# CPU.net
KiCad netlist of a schematic drawn in Altium Designer
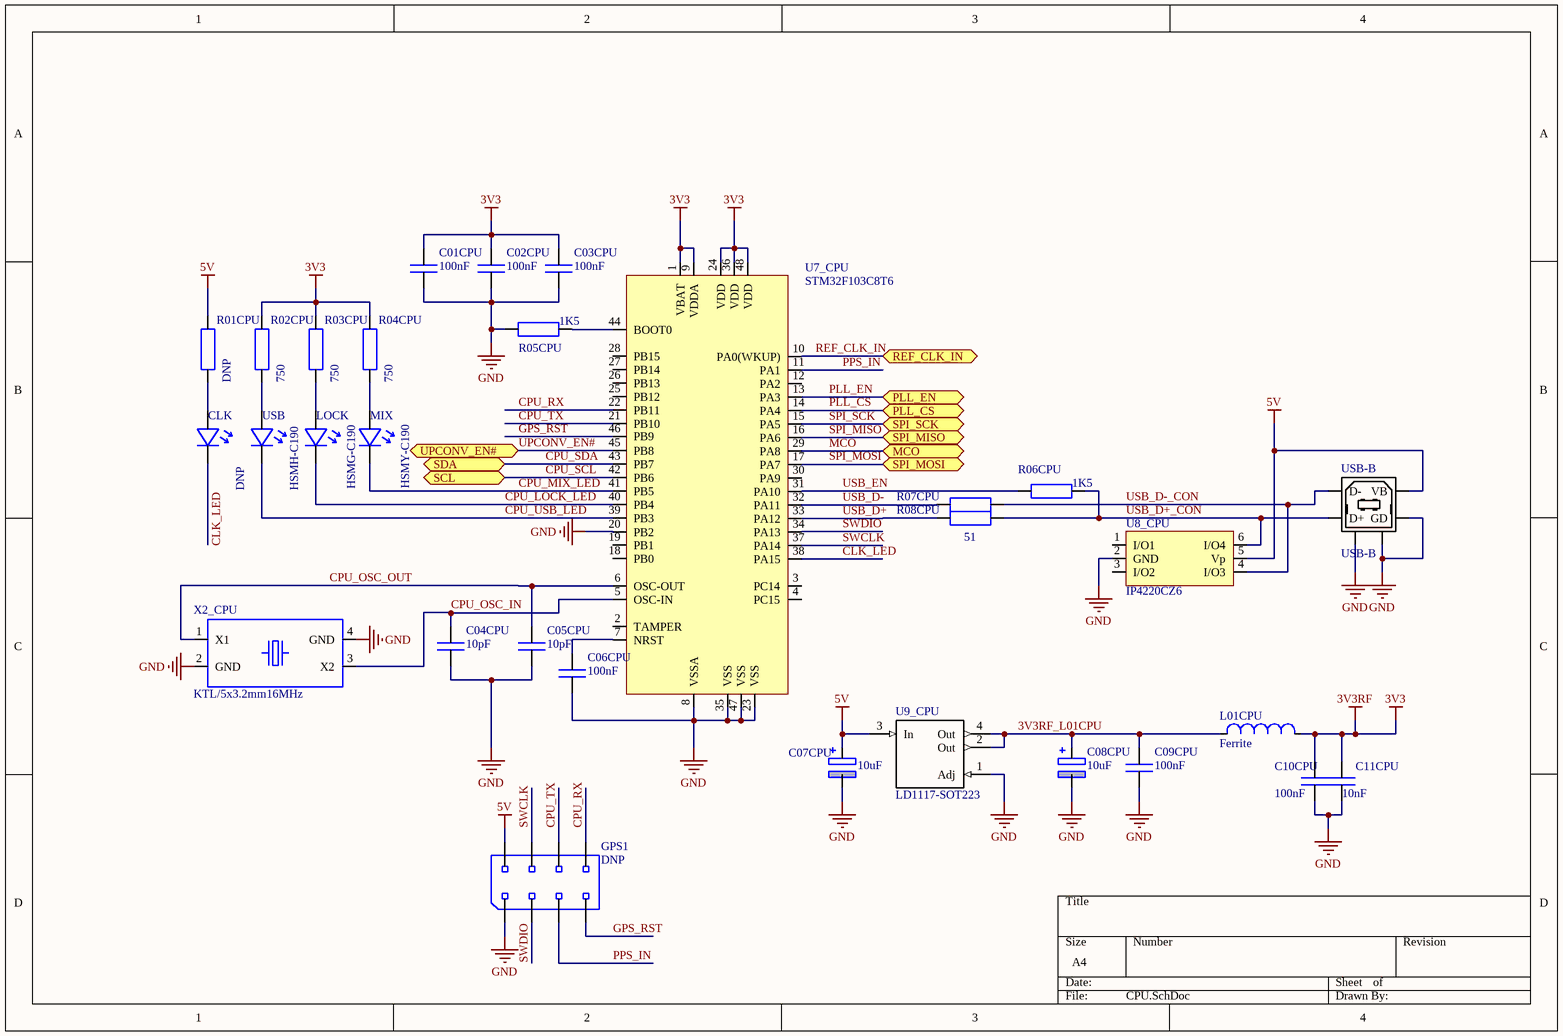
[diagram p0: CPU.SchDoc]

(export (version "E")
  (design (tool "Eeschema 10.0.6"))
  (components
    (comp (ref "C01CPU")
      (value "100nF")
      (footprint "smd C0603_0.80")
      (description "smd capaciteit, verp.0603, 100nF")
      (fields (field (name "PART NUMBER") "CSMD603/100nF"))
      (libsource (lib "CDE_Library") (part "CSMD603/100nF"))
    )
    (comp (ref "C02CPU")
      (value "100nF")
      (footprint "smd C0603_0.80")
      (description "smd capaciteit, verp.0603, 100nF")
      (fields (field (name "PART NUMBER") "CSMD603/100nF"))
      (libsource (lib "CDE_Library") (part "CSMD603/100nF"))
    )
    (comp (ref "C03CPU")
      (value "100nF")
      (footprint "smd C0603_0.80")
      (description "smd capaciteit, verp.0603, 100nF")
      (fields (field (name "PART NUMBER") "CSMD603/100nF"))
      (libsource (lib "CDE_Library") (part "CSMD603/100nF"))
    )
    (comp (ref "C04CPU")
      (value "10pF")
      (footprint "smd C0603_0.80")
      (description "smd capaciteit, verp.0603, 10pF")
      (fields (field (name "PART NUMBER") "CSMD603/10pF"))
      (libsource (lib "CDE_Library") (part "CSMD603/10pF"))
    )
    (comp (ref "C05CPU")
      (value "10pF")
      (footprint "smd C0603_0.80")
      (description "smd capaciteit, verp.0603, 10pF")
      (fields (field (name "PART NUMBER") "CSMD603/10pF"))
      (libsource (lib "CDE_Library") (part "CSMD603/10pF"))
    )
    (comp (ref "C06CPU")
      (value "100nF")
      (footprint "smd C0603_0.80")
      (description "smd capaciteit, verp.0603, 100nF")
      (fields (field (name "PART NUMBER") "CSMD603/100nF"))
      (libsource (lib "CDE_Library") (part "CSMD603/100nF"))
    )
    (comp (ref "C07CPU")
      (value "10uF")
      (footprint "smd C1206 polar")
      (description "smd capaciteit, tantalium, verp.1206, 10uF/10V")
      (fields (field (name "PART NUMBER") "CSMD1206/10uF/10V"))
      (libsource (lib "CDE_Library") (part "CSMD1206/10uF/10V"))
    )
    (comp (ref "C08CPU")
      (value "10uF")
      (footprint "smd C1206 polar")
      (description "smd capaciteit, tantalium, verp.1206, 10uF/10V")
      (fields (field (name "PART NUMBER") "CSMD1206/10uF/10V"))
      (libsource (lib "CDE_Library") (part "CSMD1206/10uF/10V"))
    )
    (comp (ref "C09CPU")
      (value "100nF")
      (footprint "smd C0603_0.80")
      (description "smd capaciteit, verp.0603, 100nF")
      (fields (field (name "PART NUMBER") "CSMD603/100nF"))
      (libsource (lib "CDE_Library") (part "CSMD603/100nF"))
    )
    (comp (ref "C10CPU")
      (value "100nF")
      (footprint "smd C0603_0.80")
      (description "smd capaciteit, verp.0603, 100nF")
      (fields (field (name "PART NUMBER") "CSMD603/100nF"))
      (libsource (lib "CDE_Library") (part "CSMD603/100nF"))
    )
    (comp (ref "C11CPU")
      (value "10nF")
      (footprint "smd C0603_0.80")
      (description "smd capaciteit, verp.0603, 100nF")
      (fields (field (name "PART NUMBER") "CSMD603/100nF"))
      (libsource (lib "CDE_Library") (part "CSMD603/100nF"))
    )
    (comp (ref "CLK")
      (value "DNP")
      (footprint "led HSMH-C190 (Avago Technologies)")
      (description "led smd rood, Avago Techn., HSMH-C190")
      (libsource (lib "CDE_Library") (part "HSMH-C190"))
    )
    (comp (ref "GPS1")
      (value "DNP")
      (footprint "hdr 2x4")
      (description "pcb header recht 2x4  pitch 100mil")
      (fields (field (name "PART NUMBER") "CON HDR 2x4"))
      (libsource (lib "CDE_Library") (part "CON HDR 2x4"))
    )
    (comp (ref "L01CPU")
      (value "Ferrite")
      (footprint "smd C0805")
      (description "Ferrite bead, 0805 package")
      (libsource (lib "CDE_Library") (part "Ferrite 0805"))
    )
    (comp (ref "LOCK")
      (value "HSMG-C190")
      (footprint "led HSMH-C190 (Avago Technologies)")
      (description "led smd groen, Avago Techn., HSMG-C190")
      (libsource (lib "CDE_Library") (part "HSMG-C190"))
    )
    (comp (ref "MIX")
      (value "HSMY-C190")
      (footprint "led HSMH-C190 (Avago Technologies)")
      (description "led smd geel, Avago Techn., HSMY-C190")
      (libsource (lib "CDE_Library") (part "HSMY-C190"))
    )
    (comp (ref "R01CPU")
      (value "DNP")
      (footprint "smd C0603_0.45")
      (description "weerstand SMD603, 470R")
      (libsource (lib "CDE_Library") (part "470R/603"))
    )
    (comp (ref "R02CPU")
      (value "750")
      (footprint "smd C0603_0.45")
      (description "weerstand SMD603, 470R")
      (libsource (lib "CDE_Library") (part "470R/603"))
    )
    (comp (ref "R03CPU")
      (value "750")
      (footprint "smd C0603_0.45")
      (description "weerstand SMD603, 470R")
      (libsource (lib "CDE_Library") (part "470R/603"))
    )
    (comp (ref "R04CPU")
      (value "750")
      (footprint "smd C0603_0.45")
      (description "weerstand SMD603, 470R")
      (libsource (lib "CDE_Library") (part "470R/603"))
    )
    (comp (ref "R05CPU")
      (value "1K5")
      (footprint "smd C0603_0.45")
      (description "weerstand SMD603, 1K5")
      (libsource (lib "CDE_Library") (part "1K5/603"))
    )
    (comp (ref "R06CPU")
      (value "1K5")
      (footprint "smd C0603_0.45")
      (description "weerstand SMD603, 1K5")
      (libsource (lib "CDE_Library") (part "1K5/603"))
    )
    (comp (ref "R07CPU")
      (value "51")
      (footprint "smd C0603_0.45")
      (description "weerstand SMD603, 22R")
      (libsource (lib "CDE_Library") (part "22R/603"))
    )
    (comp (ref "R08CPU")
      (value "51")
      (footprint "smd C0603_0.45")
      (description "weerstand SMD603, 22R")
      (libsource (lib "CDE_Library") (part "22R/603"))
    )
    (comp (ref "U7_CPU")
      (value "STM32F103C8T6")
      (footprint "TSQFP50P900X900X160-48N")
      (libsource (lib "library") (part "STM32F100xx"))
    )
    (comp (ref "U8_CPU")
      (value "IP4220CZ6")
      (footprint "smd SOT-457")
      (description "Dual USB 2.0 integrated ESD protection")
      (libsource (lib "CDE_Library") (part "IP4220CZ6"))
    )
    (comp (ref "U9_CPU")
      (value "LD1117-SOT223")
      (footprint "SOT223")
      (libsource (lib "vh_altium_library") (part "LD1117-SOT223"))
    )
    (comp (ref "USB")
      (value "HSMH-C190")
      (footprint "led HSMH-C190 (Avago Technologies)")
      (description "led smd rood, Avago Techn., HSMH-C190")
      (libsource (lib "CDE_Library") (part "HSMH-C190"))
    )
    (comp (ref "USB-B")
      (value "USB-B")
      (footprint "USB-B")
      (description "USB B DEVICE CONNECTOR")
      (libsource (lib "vh_altium_library") (part "USB-B"))
    )
    (comp (ref "X2_CPU")
      (value "KTL/5x3.2mm16MHz")
      (footprint "smd KTL 5x3.2")
      (description "TXC Xtal 16.000 MHz, 5x3.2mm")
      (fields (field (name "PART NUMBER") "KTL/5x3.2mm 16MHz"))
      (libsource (lib "CDE_Library_local") (part "KTL/5x3.2mm 16MHz"))
    )
  )
  (nets
    (net (code "1") (name "/3V3RF_L01CPU") (class "Default")
      (node (ref "C08CPU") (pin "1") (pintype "passive"))
      (node (ref "C09CPU") (pin "2") (pintype "passive"))
      (node (ref "L01CPU") (pin "1") (pintype "passive"))
      (node (ref "U9_CPU") (pin "2") (pinfunction "Out_2") (pintype "output"))
      (node (ref "U9_CPU") (pin "4") (pinfunction "Out_4") (pintype "output"))
    )
    (net (code "2") (name "/CLK_LED") (class "Default")
      (node (ref "CLK") (pin "2") (pintype "passive"))
      (node (ref "U7_CPU") (pin "38") (pinfunction "PA15_38") (pintype "passive"))
    )
    (net (code "3") (name "/CPU_LOCK_LED") (class "Default")
      (node (ref "LOCK") (pin "2") (pintype "passive"))
      (node (ref "U7_CPU") (pin "40") (pinfunction "PB4_40") (pintype "passive"))
    )
    (net (code "4") (name "/CPU_MIX_LED") (class "Default")
      (node (ref "MIX") (pin "2") (pintype "passive"))
      (node (ref "U7_CPU") (pin "41") (pinfunction "PB5_41") (pintype "passive"))
    )
    (net (code "5") (name "/CPU_OSC_IN") (class "Default")
      (node (ref "C04CPU") (pin "2") (pintype "passive"))
      (node (ref "U7_CPU") (pin "5") (pinfunction "OSC-IN_5") (pintype "passive"))
      (node (ref "X2_CPU") (pin "3") (pinfunction "X2_3") (pintype "passive"))
    )
    (net (code "6") (name "/CPU_OSC_OUT") (class "Default")
      (node (ref "C05CPU") (pin "2") (pintype "passive"))
      (node (ref "U7_CPU") (pin "6") (pinfunction "OSC-OUT_6") (pintype "passive"))
      (node (ref "X2_CPU") (pin "1") (pinfunction "X1_1") (pintype "passive"))
    )
    (net (code "7") (name "/CPU_RX") (class "Default")
      (node (ref "GPS1") (pin "8") (pintype "passive"))
      (node (ref "U7_CPU") (pin "22") (pinfunction "PB11_22") (pintype "passive"))
    )
    (net (code "8") (name "/CPU_SCL") (class "Default")
      (node (ref "U7_CPU") (pin "42") (pinfunction "PB6_42") (pintype "passive"))
    )
    (net (code "9") (name "/CPU_SDA") (class "Default")
      (node (ref "U7_CPU") (pin "43") (pinfunction "PB7_43") (pintype "passive"))
    )
    (net (code "10") (name "/CPU_TX") (class "Default")
      (node (ref "GPS1") (pin "6") (pintype "passive"))
      (node (ref "U7_CPU") (pin "21") (pinfunction "PB10_21") (pintype "passive"))
    )
    (net (code "11") (name "/CPU_USB_LED") (class "Default")
      (node (ref "U7_CPU") (pin "39") (pinfunction "PB3_39") (pintype "passive"))
      (node (ref "USB") (pin "2") (pintype "passive"))
    )
    (net (code "12") (name "/GPS_RST") (class "Default")
      (node (ref "GPS1") (pin "7") (pintype "passive"))
      (node (ref "U7_CPU") (pin "46") (pinfunction "PB9_46") (pintype "passive"))
    )
    (net (code "13") (name "/MCO") (class "Default")
      (node (ref "U7_CPU") (pin "29") (pinfunction "PA8_29") (pintype "passive"))
    )
    (net (code "14") (name "/PLL_CS") (class "Default")
      (node (ref "U7_CPU") (pin "14") (pinfunction "PA4_14") (pintype "passive"))
    )
    (net (code "15") (name "/PLL_EN") (class "Default")
      (node (ref "U7_CPU") (pin "13") (pinfunction "PA3_13") (pintype "passive"))
    )
    (net (code "16") (name "/PPS_IN") (class "Default")
      (node (ref "GPS1") (pin "5") (pintype "passive"))
      (node (ref "U7_CPU") (pin "11") (pinfunction "PA1_11") (pintype "passive"))
    )
    (net (code "17") (name "/REF_CLK_IN") (class "Default")
      (node (ref "U7_CPU") (pin "10") (pinfunction "PA0(WKUP)_10") (pintype "passive"))
    )
    (net (code "18") (name "/SPI_MISO") (class "Default")
      (node (ref "U7_CPU") (pin "16") (pinfunction "PA6_16") (pintype "passive"))
    )
    (net (code "19") (name "/SPI_MOSI") (class "Default")
      (node (ref "U7_CPU") (pin "17") (pinfunction "PA7_17") (pintype "passive"))
    )
    (net (code "20") (name "/SPI_SCK") (class "Default")
      (node (ref "U7_CPU") (pin "15") (pinfunction "PA5_15") (pintype "passive"))
    )
    (net (code "21") (name "/SWCLK") (class "Default")
      (node (ref "GPS1") (pin "4") (pintype "passive"))
      (node (ref "U7_CPU") (pin "37") (pinfunction "PA14_37") (pintype "passive"))
    )
    (net (code "22") (name "/SWDIO") (class "Default")
      (node (ref "GPS1") (pin "3") (pintype "passive"))
      (node (ref "U7_CPU") (pin "34") (pinfunction "PA13_34") (pintype "passive"))
    )
    (net (code "23") (name "/UPCONV_EN#") (class "Default")
      (node (ref "U7_CPU") (pin "45") (pinfunction "PB8_45") (pintype "passive"))
    )
    (net (code "24") (name "/USB_D+") (class "Default")
      (node (ref "R08CPU") (pin "1") (pintype "passive"))
      (node (ref "U7_CPU") (pin "33") (pinfunction "PA12_33") (pintype "passive"))
    )
    (net (code "25") (name "/USB_D+_CON") (class "Default")
      (node (ref "R06CPU") (pin "2") (pintype "passive"))
      (node (ref "R08CPU") (pin "2") (pintype "passive"))
      (node (ref "U8_CPU") (pin "6") (pinfunction "I/O4_6") (pintype "passive"))
      (node (ref "USB-B") (pin "3") (pinfunction "D+_3") (pintype "passive"))
    )
    (net (code "26") (name "/USB_D-") (class "Default")
      (node (ref "R07CPU") (pin "1") (pintype "passive"))
      (node (ref "U7_CPU") (pin "32") (pinfunction "PA11_32") (pintype "passive"))
    )
    (net (code "27") (name "/USB_D-_CON") (class "Default")
      (node (ref "R07CPU") (pin "2") (pintype "passive"))
      (node (ref "U8_CPU") (pin "4") (pinfunction "I/O3_4") (pintype "passive"))
      (node (ref "USB-B") (pin "2") (pinfunction "D-_2") (pintype "passive"))
    )
    (net (code "28") (name "/USB_EN") (class "Default")
      (node (ref "R06CPU") (pin "1") (pintype "passive"))
      (node (ref "U7_CPU") (pin "31") (pinfunction "PA10_31") (pintype "passive"))
    )
    (net (code "29") (name "3V3") (class "Default")
      (node (ref "C01CPU") (pin "2") (pintype "passive"))
      (node (ref "C02CPU") (pin "2") (pintype "passive"))
      (node (ref "C03CPU") (pin "2") (pintype "passive"))
      (node (ref "C10CPU") (pin "2") (pintype "passive"))
      (node (ref "C11CPU") (pin "2") (pintype "passive"))
      (node (ref "L01CPU") (pin "2") (pintype "passive"))
      (node (ref "R02CPU") (pin "2") (pintype "passive"))
      (node (ref "R03CPU") (pin "2") (pintype "passive"))
      (node (ref "R04CPU") (pin "2") (pintype "passive"))
      (node (ref "U7_CPU") (pin "1") (pinfunction "VBAT_1") (pintype "passive"))
      (node (ref "U7_CPU") (pin "24") (pinfunction "VDD_24") (pintype "passive"))
      (node (ref "U7_CPU") (pin "36") (pinfunction "VDD_36") (pintype "passive"))
      (node (ref "U7_CPU") (pin "48") (pinfunction "VDD_48") (pintype "passive"))
      (node (ref "U7_CPU") (pin "9") (pinfunction "VDDA_9") (pintype "passive"))
    )
    (net (code "30") (name "5V") (class "Default")
      (node (ref "C07CPU") (pin "1") (pintype "passive"))
      (node (ref "GPS1") (pin "2") (pintype "passive"))
      (node (ref "R01CPU") (pin "2") (pintype "passive"))
      (node (ref "U8_CPU") (pin "5") (pinfunction "Vp_5") (pintype "passive"))
      (node (ref "U9_CPU") (pin "3") (pinfunction "In_3") (pintype "input"))
      (node (ref "USB-B") (pin "1") (pinfunction "VB_1") (pintype "passive"))
    )
    (net (code "31") (name "GND") (class "Default")
      (node (ref "C01CPU") (pin "1") (pintype "passive"))
      (node (ref "C02CPU") (pin "1") (pintype "passive"))
      (node (ref "C03CPU") (pin "1") (pintype "passive"))
      (node (ref "C04CPU") (pin "1") (pintype "passive"))
      (node (ref "C05CPU") (pin "1") (pintype "passive"))
      (node (ref "C06CPU") (pin "1") (pintype "passive"))
      (node (ref "C07CPU") (pin "2") (pintype "passive"))
      (node (ref "C08CPU") (pin "2") (pintype "passive"))
      (node (ref "C09CPU") (pin "1") (pintype "passive"))
      (node (ref "C10CPU") (pin "1") (pintype "passive"))
      (node (ref "C11CPU") (pin "1") (pintype "passive"))
      (node (ref "GPS1") (pin "1") (pintype "passive"))
      (node (ref "R05CPU") (pin "1") (pintype "passive"))
      (node (ref "U7_CPU") (pin "20") (pinfunction "PB2_20") (pintype "passive"))
      (node (ref "U7_CPU") (pin "23") (pinfunction "VSS_23") (pintype "passive"))
      (node (ref "U7_CPU") (pin "35") (pinfunction "VSS_35") (pintype "passive"))
      (node (ref "U7_CPU") (pin "47") (pinfunction "VSS_47") (pintype "passive"))
      (node (ref "U7_CPU") (pin "8") (pinfunction "VSSA_8") (pintype "passive"))
      (node (ref "U8_CPU") (pin "2") (pinfunction "GND_2") (pintype "passive"))
      (node (ref "U9_CPU") (pin "1") (pinfunction "Adj_1") (pintype "input"))
      (node (ref "USB-B") (pin "4") (pinfunction "GD_4") (pintype "passive"))
      (node (ref "USB-B") (pin "5") (pintype "passive"))
      (node (ref "USB-B") (pin "6") (pintype "passive"))
      (node (ref "X2_CPU") (pin "2") (pinfunction "GND_2") (pintype "passive"))
      (node (ref "X2_CPU") (pin "4") (pinfunction "GND_4") (pintype "passive"))
    )
    (net (code "32") (name "Net-(CLK-Pad1)") (class "Default")
      (node (ref "CLK") (pin "1") (pintype "passive"))
      (node (ref "R01CPU") (pin "1") (pintype "passive"))
    )
    (net (code "33") (name "Net-(LOCK-Pad1)") (class "Default")
      (node (ref "LOCK") (pin "1") (pintype "passive"))
      (node (ref "R03CPU") (pin "1") (pintype "passive"))
    )
    (net (code "34") (name "Net-(MIX-Pad1)") (class "Default")
      (node (ref "MIX") (pin "1") (pintype "passive"))
      (node (ref "R04CPU") (pin "1") (pintype "passive"))
    )
    (net (code "35") (name "Net-(R02CPU-Pad1)") (class "Default")
      (node (ref "R02CPU") (pin "1") (pintype "passive"))
      (node (ref "USB") (pin "1") (pintype "passive"))
    )
    (net (code "36") (name "Net-(U7_CPU-BOOT0)") (class "Default")
      (node (ref "R05CPU") (pin "2") (pintype "passive"))
      (node (ref "U7_CPU") (pin "44") (pinfunction "BOOT0_44") (pintype "passive"))
    )
    (net (code "37") (name "Net-(U7_CPU-NRST)") (class "Default")
      (node (ref "C06CPU") (pin "2") (pintype "passive"))
      (node (ref "U7_CPU") (pin "7") (pinfunction "NRST_7") (pintype "passive"))
    )
    (net (code "38") (name "unconnected-(U7_CPU-PA2-Pad12)") (class "Default")
      (node (ref "U7_CPU") (pin "12") (pinfunction "PA2_12") (pintype "passive"))
    )
    (net (code "39") (name "unconnected-(U7_CPU-PA9-Pad30)") (class "Default")
      (node (ref "U7_CPU") (pin "30") (pinfunction "PA9_30") (pintype "passive"))
    )
    (net (code "40") (name "unconnected-(U7_CPU-PB0-Pad18)") (class "Default")
      (node (ref "U7_CPU") (pin "18") (pinfunction "PB0_18") (pintype "passive"))
    )
    (net (code "41") (name "unconnected-(U7_CPU-PB1-Pad19)") (class "Default")
      (node (ref "U7_CPU") (pin "19") (pinfunction "PB1_19") (pintype "passive"))
    )
    (net (code "42") (name "unconnected-(U7_CPU-PB12-Pad25)") (class "Default")
      (node (ref "U7_CPU") (pin "25") (pinfunction "PB12_25") (pintype "passive"))
    )
    (net (code "43") (name "unconnected-(U7_CPU-PB13-Pad26)") (class "Default")
      (node (ref "U7_CPU") (pin "26") (pinfunction "PB13_26") (pintype "passive"))
    )
    (net (code "44") (name "unconnected-(U7_CPU-PB14-Pad27)") (class "Default")
      (node (ref "U7_CPU") (pin "27") (pinfunction "PB14_27") (pintype "passive"))
    )
    (net (code "45") (name "unconnected-(U7_CPU-PB15-Pad28)") (class "Default")
      (node (ref "U7_CPU") (pin "28") (pinfunction "PB15_28") (pintype "passive"))
    )
    (net (code "46") (name "unconnected-(U7_CPU-PC14-Pad3)") (class "Default")
      (node (ref "U7_CPU") (pin "3") (pinfunction "PC14_3") (pintype "passive"))
    )
    (net (code "47") (name "unconnected-(U7_CPU-PC15-Pad4)") (class "Default")
      (node (ref "U7_CPU") (pin "4") (pinfunction "PC15_4") (pintype "passive"))
    )
    (net (code "48") (name "unconnected-(U7_CPU-TAMPER-Pad2)") (class "Default")
      (node (ref "U7_CPU") (pin "2") (pinfunction "TAMPER_2") (pintype "passive"))
    )
    (net (code "49") (name "unconnected-(U8_CPU-I{slash}O1-Pad1)") (class "Default")
      (node (ref "U8_CPU") (pin "1") (pinfunction "I/O1_1") (pintype "passive"))
    )
    (net (code "50") (name "unconnected-(U8_CPU-I{slash}O2-Pad3)") (class "Default")
      (node (ref "U8_CPU") (pin "3") (pinfunction "I/O2_3") (pintype "passive"))
    )
  )
)
